# 03_SRAD_Current_Amplification.net
KiCad netlist of a schematic drawn in Altium Designer
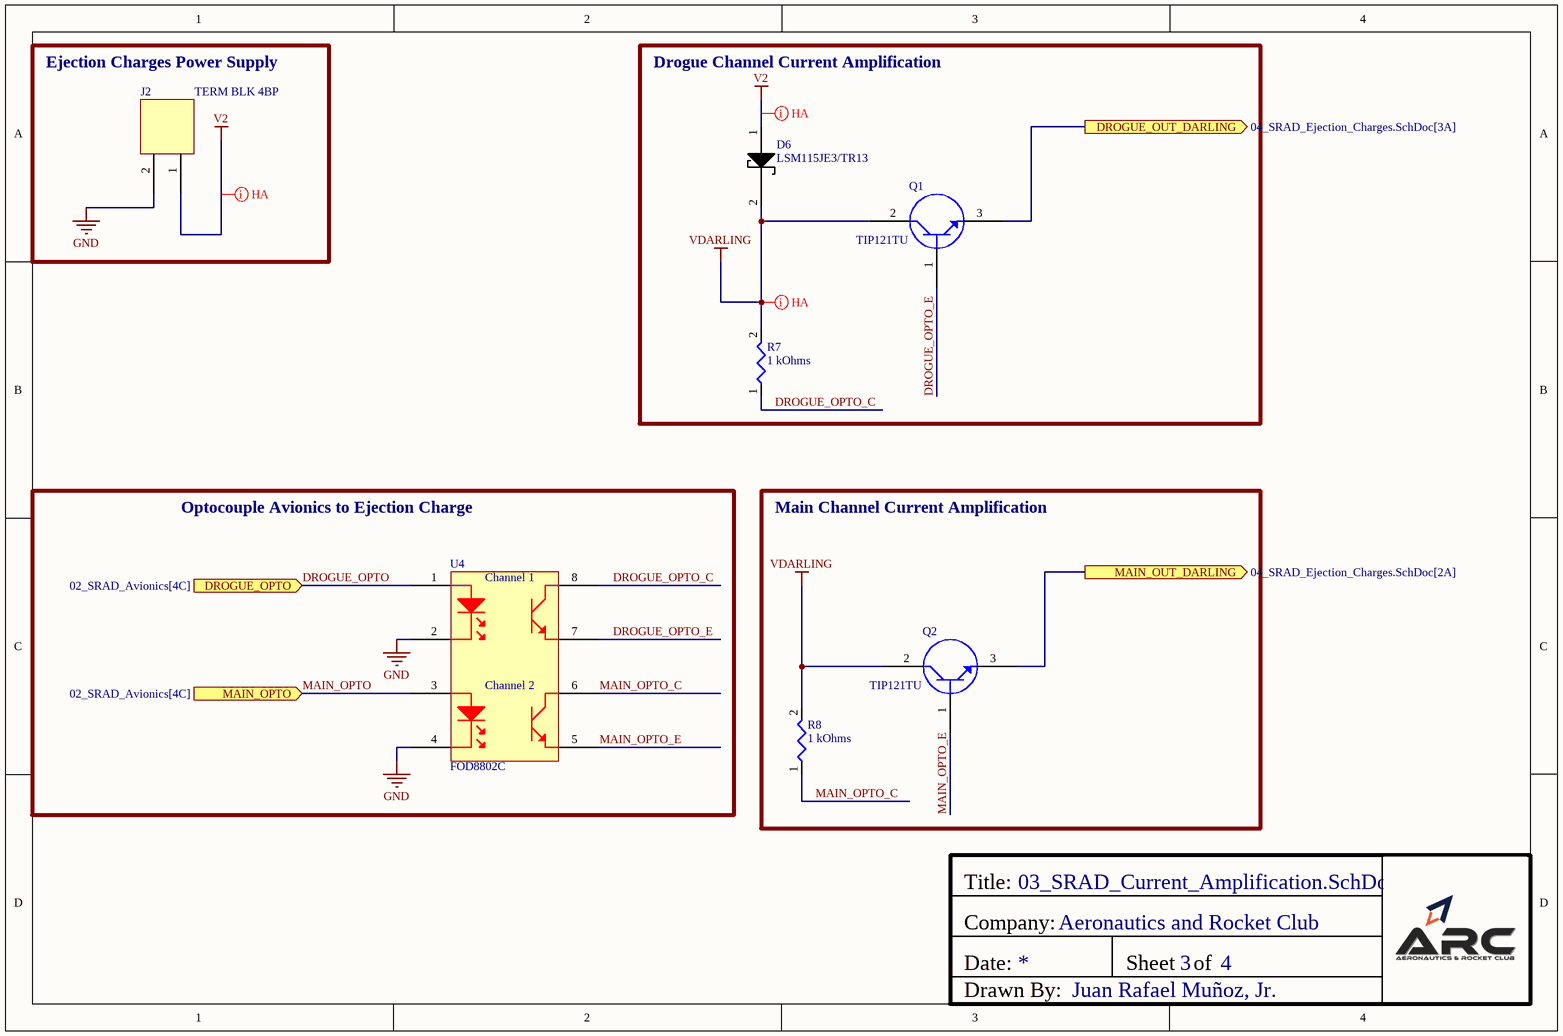
[diagram p0: 03_SRAD_Current_Amplification.SchDoc]

(export (version "E")
  (design (tool "Eeschema 10.0.6"))
  (components
    (comp (ref "D6")
      (value "LSM115JE3/TR13")
      (footprint "DIOM4336X33N")
      (fields (field (name "MANUFACTURER") "Microchip"))
      (libsource (lib "SRAD_SAC_Schlib") (part "DIOM4336X33N Schottky Diode"))
    )
    (comp (ref "J2")
      (value "TERM BLK 4BP")
      (footprint "PCB TERM BLK 2P 2.54MM")
      (fields
        (field (name "MANUFACTURER") "TE Connectivity")
        (field (name "MANUFACTURER PART NUMBER") "282834-2")
        (field (name "VOLTAGE") "150V")
      )
      (libsource (lib "SRAD_SAC_Schlib") (part "PCB TERM BLK 2P 2.54MM"))
    )
    (comp (ref "Q1")
      (value "TIP121TU")
      (footprint "TIP121TU DARLINGTON")
      (description "Bipolar (BJT) Transistor NPN - Darlington 80 V 5 A 2 W Through Hole TO-220-3")
      (fields (field (name "MANUFACTURER") "ON Semiconductor / Fairchild"))
      (libsource (lib "SRAD_SAC_Schlib") (part "TIP121TU"))
    )
    (comp (ref "Q2")
      (value "TIP121TU")
      (footprint "TIP121TU DARLINGTON")
      (description "Bipolar (BJT) Transistor NPN - Darlington 80 V 5 A 2 W Through Hole TO-220-3")
      (fields (field (name "MANUFACTURER") "ON Semiconductor / Fairchild"))
      (libsource (lib "SRAD_SAC_Schlib") (part "TIP121TU"))
    )
    (comp (ref "R7")
      (value "1 kOhms")
      (footprint "RESC2012X06N")
      (description "1 kOhms ±1% 0.25W, 1/4W Chip Resistor 0805 (2012 Metric) Moisture Resistant Thick Film")
      (fields
        (field (name "MANUFACTURER") "Yageo")
        (field (name "MANUFACTURER PART NUMBER") "RC0805FR-7W1KL")
      )
      (libsource (lib "SRAD_SAC_Schlib") (part "RC0805FR-7W1KL Yageo"))
    )
    (comp (ref "R8")
      (value "1 kOhms")
      (footprint "RESC2012X06N")
      (description "1 kOhms ±1% 0.25W, 1/4W Chip Resistor 0805 (2012 Metric) Moisture Resistant Thick Film")
      (fields
        (field (name "MANUFACTURER") "Yageo")
        (field (name "MANUFACTURER PART NUMBER") "RC0805FR-7W1KL")
      )
      (libsource (lib "SRAD_SAC_Schlib") (part "RC0805FR-7W1KL Yageo"))
    )
    (comp (ref "U4")
      (value "FOD8802C")
      (footprint "SOIC127P590X363-8N OPTO")
      (fields (field (name "MANUFACTURER") "ON Semiconductor"))
      (libsource (lib "SRAD_SAC_Schlib") (part "FOD8802C"))
    )
  )
  (nets
    (net (code "1") (name "/DROGUE_OPTO") (class "Default")
      (node (ref "U4") (pin "1") (pinfunction "+_1") (pintype "passive"))
    )
    (net (code "2") (name "/DROGUE_OPTO_C") (class "Default")
      (node (ref "R7") (pin "1") (pinfunction "1_1") (pintype "passive"))
      (node (ref "U4") (pin "8") (pinfunction "C1_8") (pintype "passive"))
    )
    (net (code "3") (name "/DROGUE_OPTO_E") (class "Default")
      (node (ref "Q1") (pin "1") (pinfunction "B_1") (pintype "passive"))
      (node (ref "U4") (pin "7") (pinfunction "E1_7") (pintype "passive"))
    )
    (net (code "4") (name "/DROGUE_OUT_DARLING") (class "Default")
      (node (ref "Q1") (pin "3") (pinfunction "E_3") (pintype "passive"))
    )
    (net (code "5") (name "/MAIN_OPTO") (class "Default")
      (node (ref "U4") (pin "3") (pinfunction "+_3") (pintype "passive"))
    )
    (net (code "6") (name "/MAIN_OPTO_C") (class "Default")
      (node (ref "R8") (pin "1") (pinfunction "1_1") (pintype "passive"))
      (node (ref "U4") (pin "6") (pinfunction "C2_6") (pintype "passive"))
    )
    (net (code "7") (name "/MAIN_OPTO_E") (class "Default")
      (node (ref "Q2") (pin "1") (pinfunction "B_1") (pintype "passive"))
      (node (ref "U4") (pin "5") (pinfunction "E2_5") (pintype "passive"))
    )
    (net (code "8") (name "/MAIN_OUT_DARLING") (class "Default")
      (node (ref "Q2") (pin "3") (pinfunction "E_3") (pintype "passive"))
    )
    (net (code "9") (name "GND") (class "Default")
      (node (ref "J2") (pin "2") (pinfunction "-_2") (pintype "passive"))
      (node (ref "U4") (pin "2") (pinfunction "-_2") (pintype "passive"))
      (node (ref "U4") (pin "4") (pinfunction "-_4") (pintype "passive"))
    )
    (net (code "10") (name "V2") (class "Default")
      (node (ref "D6") (pin "1") (pinfunction "+_1") (pintype "passive"))
      (node (ref "J2") (pin "1") (pinfunction "+_1") (pintype "passive"))
    )
    (net (code "11") (name "VDARLING") (class "Default")
      (node (ref "D6") (pin "2") (pinfunction "-_2") (pintype "passive"))
      (node (ref "Q1") (pin "2") (pinfunction "C_2") (pintype "passive"))
      (node (ref "Q2") (pin "2") (pinfunction "C_2") (pintype "passive"))
      (node (ref "R7") (pin "2") (pinfunction "2_2") (pintype "passive"))
      (node (ref "R8") (pin "2") (pinfunction "2_2") (pintype "passive"))
    )
  )
)
